# M220xc.net
KiCad netlist of a schematic drawn in EAGLE
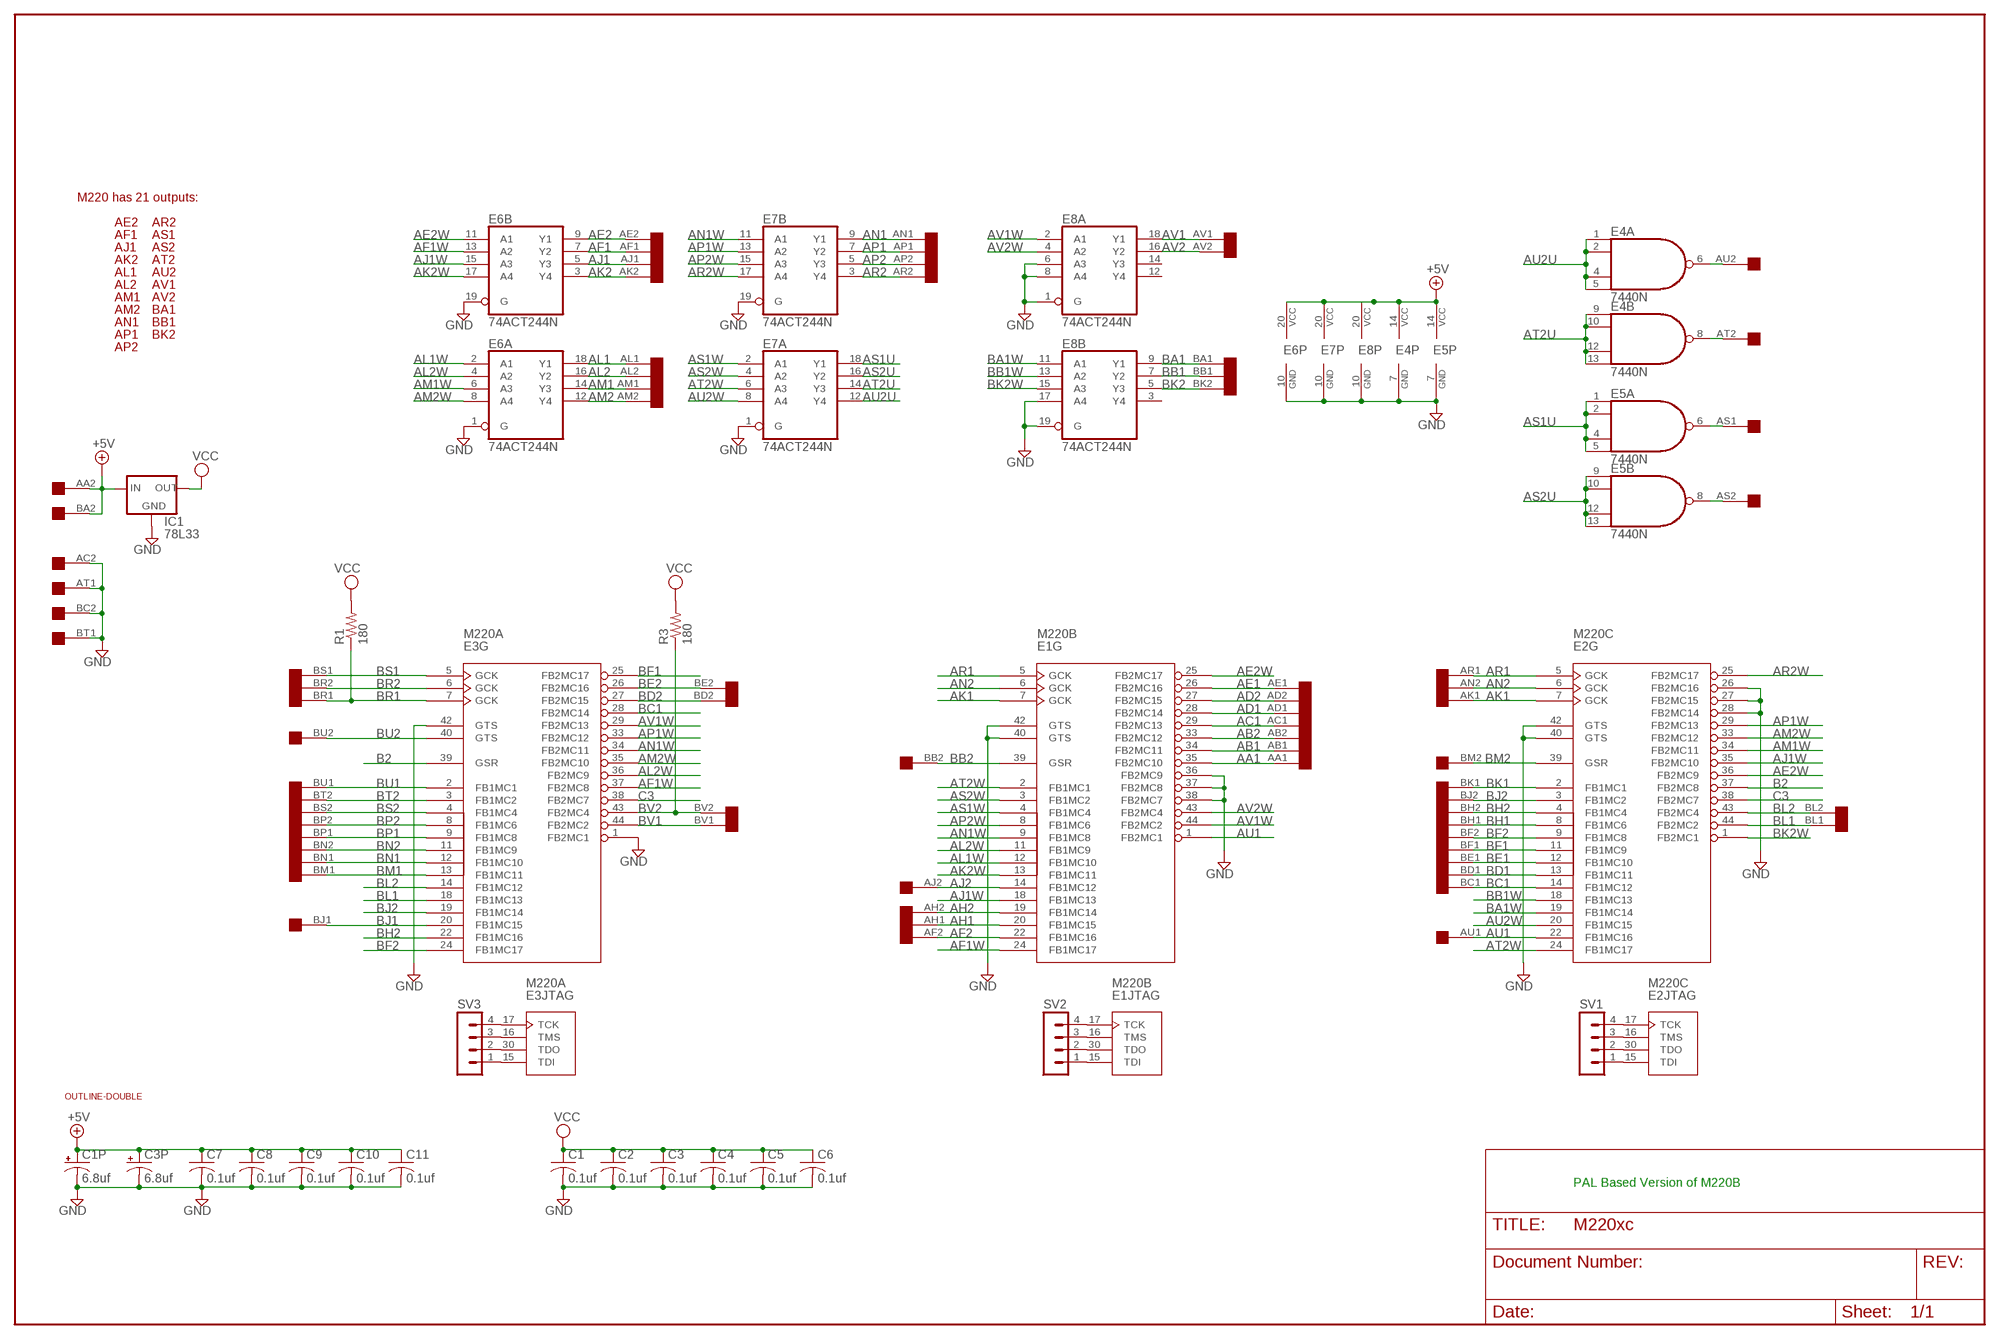
[diagram p0: schematic, sheet 1]

(export (version "E")
  (design (tool "Eeschema 10.0.6"))
  (components
    (comp (ref "C1")
      (value "0.1uf")
      (footprint "eagle-import:C050-025X075")
      (libsource (lib "eagle-import") (part "C-US050-025X075"))
    )
    (comp (ref "C1P")
      (value "6.8uf")
      (footprint "eagle-import:E15-5")
      (libsource (lib "eagle-import") (part "CPOL-USE15-5AXIAL"))
    )
    (comp (ref "C2")
      (value "0.1uf")
      (footprint "eagle-import:C050-025X075")
      (libsource (lib "eagle-import") (part "C-US050-025X075"))
    )
    (comp (ref "C3")
      (value "0.1uf")
      (footprint "eagle-import:C050-025X075")
      (libsource (lib "eagle-import") (part "C-US050-025X075"))
    )
    (comp (ref "C3P")
      (value "6.8uf")
      (footprint "eagle-import:E15-5")
      (libsource (lib "eagle-import") (part "CPOL-USE15-5AXIAL"))
    )
    (comp (ref "C4")
      (value "0.1uf")
      (footprint "eagle-import:C050-025X075")
      (libsource (lib "eagle-import") (part "C-US050-025X075"))
    )
    (comp (ref "C5")
      (value "0.1uf")
      (footprint "eagle-import:C050-025X075")
      (libsource (lib "eagle-import") (part "C-US050-025X075"))
    )
    (comp (ref "C6")
      (value "0.1uf")
      (footprint "eagle-import:C050-025X075")
      (libsource (lib "eagle-import") (part "C-US050-025X075"))
    )
    (comp (ref "C7")
      (value "0.1uf")
      (footprint "eagle-import:C050-025X075")
      (libsource (lib "eagle-import") (part "C-US050-025X075"))
    )
    (comp (ref "C8")
      (value "0.1uf")
      (footprint "eagle-import:C050-025X075")
      (libsource (lib "eagle-import") (part "C-US050-025X075"))
    )
    (comp (ref "C9")
      (value "0.1uf")
      (footprint "eagle-import:C050-025X075")
      (libsource (lib "eagle-import") (part "C-US050-025X075"))
    )
    (comp (ref "C10")
      (value "0.1uf")
      (footprint "eagle-import:C050-025X075")
      (libsource (lib "eagle-import") (part "C-US050-025X075"))
    )
    (comp (ref "C11")
      (value "0.1uf")
      (footprint "eagle-import:C050-025X075")
      (libsource (lib "eagle-import") (part "C-US050-025X075"))
    )
    (comp (ref "E1")
      (value "M220B")
      (footprint "eagle-import:PLCC-S44")
      (libsource (lib "eagle-import") (part "XC9536-44"))
    )
    (comp (ref "E2")
      (value "M220C")
      (footprint "eagle-import:PLCC-S44")
      (libsource (lib "eagle-import") (part "XC9536-44"))
    )
    (comp (ref "E3")
      (value "M220A")
      (footprint "eagle-import:PLCC-S44")
      (libsource (lib "eagle-import") (part "XC9536-44"))
    )
    (comp (ref "E4")
      (value "7440N")
      (footprint "eagle-import:DIL14")
      (libsource (lib "eagle-import") (part "7420NS"))
    )
    (comp (ref "E5")
      (value "7440N")
      (footprint "eagle-import:DIL14")
      (libsource (lib "eagle-import") (part "7420NS"))
    )
    (comp (ref "E6")
      (value "74ACT244N")
      (footprint "eagle-import:DIL20")
      (libsource (lib "eagle-import") (part "74244NS"))
    )
    (comp (ref "E7")
      (value "74ACT244N")
      (footprint "eagle-import:DIL20")
      (libsource (lib "eagle-import") (part "74244NS"))
    )
    (comp (ref "E8")
      (value "74ACT244N")
      (footprint "eagle-import:DIL20")
      (libsource (lib "eagle-import") (part "74244NS"))
    )
    (comp (ref "IC1")
      (value "78L33")
      (footprint "eagle-import:78LXX")
      (libsource (lib "eagle-import") (part "78LXX"))
    )
    (comp (ref "R1")
      (value "180")
      (footprint "eagle-import:0207_10")
      (libsource (lib "eagle-import") (part "R-US_0207/10"))
    )
    (comp (ref "R3")
      (value "180")
      (footprint "eagle-import:0207_10")
      (libsource (lib "eagle-import") (part "R-US_0207/10"))
    )
    (comp (ref "SV1")
      (value "MA04-1")
      (footprint "eagle-import:MA04-1")
      (libsource (lib "eagle-import") (part "MA04-1"))
    )
    (comp (ref "SV2")
      (value "MA04-1")
      (footprint "eagle-import:MA04-1")
      (libsource (lib "eagle-import") (part "MA04-1"))
    )
    (comp (ref "SV3")
      (value "MA04-1")
      (footprint "eagle-import:MA04-1")
      (libsource (lib "eagle-import") (part "MA04-1"))
    )
    (comp (ref "U$1")
      (value "DOUBLE")
      (footprint "eagle-import:EDGE-CON4")
      (libsource (lib "eagle-import") (part "DOUBLE"))
    )
    (comp (ref "U$2")
      (value "OUTLINE-DOUBLE")
      (footprint "eagle-import:DOUBLE")
      (libsource (lib "eagle-import") (part "OUTLINE-DOUBLE"))
    )
  )
  (nets
    (net (code "1") (name "+5V") (class "Default")
      (node (ref "C10") (pin "1") (pinfunction "1_1") (pintype "passive"))
      (node (ref "C11") (pin "1") (pinfunction "1_1") (pintype "passive"))
      (node (ref "C1P") (pin "+") (pinfunction "+_+") (pintype "passive"))
      (node (ref "C3P") (pin "+") (pinfunction "+_+") (pintype "passive"))
      (node (ref "C7") (pin "1") (pinfunction "1_1") (pintype "passive"))
      (node (ref "C8") (pin "1") (pinfunction "1_1") (pintype "passive"))
      (node (ref "C9") (pin "1") (pinfunction "1_1") (pintype "passive"))
      (node (ref "E4") (pin "14") (pinfunction "VCC_14") (pintype "power_in"))
      (node (ref "E5") (pin "14") (pinfunction "VCC_14") (pintype "power_in"))
      (node (ref "E6") (pin "20") (pinfunction "VCC_20") (pintype "power_in"))
      (node (ref "E7") (pin "20") (pinfunction "VCC_20") (pintype "power_in"))
      (node (ref "E8") (pin "20") (pinfunction "VCC_20") (pintype "power_in"))
      (node (ref "IC1") (pin "IN") (pinfunction "IN_IN") (pintype "input"))
      (node (ref "U$1") (pin "AA2") (pinfunction "1_AA2") (pintype "bidirectional"))
      (node (ref "U$1") (pin "BA2") (pinfunction "1_BA2") (pintype "bidirectional"))
    )
    (net (code "2") (name "/AA1") (class "Default")
      (node (ref "E1") (pin "35") (pinfunction "FB2MC10_35") (pintype "bidirectional"))
      (node (ref "U$1") (pin "AA1") (pinfunction "1_AA1") (pintype "bidirectional"))
    )
    (net (code "3") (name "/AB1") (class "Default")
      (node (ref "E1") (pin "34") (pinfunction "FB2MC11_34") (pintype "bidirectional"))
      (node (ref "U$1") (pin "AB1") (pinfunction "1_AB1") (pintype "bidirectional"))
    )
    (net (code "4") (name "/AB2") (class "Default")
      (node (ref "E1") (pin "33") (pinfunction "FB2MC12_33") (pintype "bidirectional"))
      (node (ref "U$1") (pin "AB2") (pinfunction "1_AB2") (pintype "bidirectional"))
    )
    (net (code "5") (name "/AC1") (class "Default")
      (node (ref "E1") (pin "29") (pinfunction "FB2MC13_29") (pintype "bidirectional"))
      (node (ref "U$1") (pin "AC1") (pinfunction "1_AC1") (pintype "bidirectional"))
    )
    (net (code "6") (name "/AD1") (class "Default")
      (node (ref "E1") (pin "28") (pinfunction "FB2MC14_28") (pintype "bidirectional"))
      (node (ref "U$1") (pin "AD1") (pinfunction "1_AD1") (pintype "bidirectional"))
    )
    (net (code "7") (name "/AD2") (class "Default")
      (node (ref "E1") (pin "27") (pinfunction "FB2MC15_27") (pintype "bidirectional"))
      (node (ref "U$1") (pin "AD2") (pinfunction "1_AD2") (pintype "bidirectional"))
    )
    (net (code "8") (name "/AE1") (class "Default")
      (node (ref "E1") (pin "26") (pinfunction "FB2MC16_26") (pintype "bidirectional"))
      (node (ref "U$1") (pin "AE1") (pinfunction "1_AE1") (pintype "bidirectional"))
    )
    (net (code "9") (name "/AE2") (class "Default")
      (node (ref "E6") (pin "9") (pinfunction "Y1_9") (pintype "tri_state"))
      (node (ref "U$1") (pin "AE2") (pinfunction "1_AE2") (pintype "bidirectional"))
    )
    (net (code "10") (name "/AE2W") (class "Default")
      (node (ref "E1") (pin "25") (pinfunction "FB2MC17_25") (pintype "bidirectional"))
      (node (ref "E2") (pin "36") (pinfunction "FB2MC9_36") (pintype "bidirectional"))
      (node (ref "E6") (pin "11") (pinfunction "A1_11") (pintype "input"))
    )
    (net (code "11") (name "/AF1") (class "Default")
      (node (ref "E6") (pin "7") (pinfunction "Y2_7") (pintype "tri_state"))
      (node (ref "U$1") (pin "AF1") (pinfunction "1_AF1") (pintype "bidirectional"))
    )
    (net (code "12") (name "/AF1W") (class "Default")
      (node (ref "E1") (pin "24") (pinfunction "FB1MC17_24") (pintype "bidirectional"))
      (node (ref "E3") (pin "37") (pinfunction "FB2MC8_37") (pintype "bidirectional"))
      (node (ref "E6") (pin "13") (pinfunction "A2_13") (pintype "input"))
    )
    (net (code "13") (name "/AF2") (class "Default")
      (node (ref "E1") (pin "22") (pinfunction "FB1MC16_22") (pintype "bidirectional"))
      (node (ref "U$1") (pin "AF2") (pinfunction "1_AF2") (pintype "bidirectional"))
    )
    (net (code "14") (name "/AH1") (class "Default")
      (node (ref "E1") (pin "20") (pinfunction "FB1MC15_20") (pintype "bidirectional"))
      (node (ref "U$1") (pin "AH1") (pinfunction "1_AH1") (pintype "bidirectional"))
    )
    (net (code "15") (name "/AH2") (class "Default")
      (node (ref "E1") (pin "19") (pinfunction "FB1MC14_19") (pintype "bidirectional"))
      (node (ref "U$1") (pin "AH2") (pinfunction "1_AH2") (pintype "bidirectional"))
    )
    (net (code "16") (name "/AJ1") (class "Default")
      (node (ref "E6") (pin "5") (pinfunction "Y3_5") (pintype "tri_state"))
      (node (ref "U$1") (pin "AJ1") (pinfunction "1_AJ1") (pintype "bidirectional"))
    )
    (net (code "17") (name "/AJ1W") (class "Default")
      (node (ref "E1") (pin "18") (pinfunction "FB1MC13_18") (pintype "bidirectional"))
      (node (ref "E2") (pin "35") (pinfunction "FB2MC10_35") (pintype "bidirectional"))
      (node (ref "E6") (pin "15") (pinfunction "A3_15") (pintype "input"))
    )
    (net (code "18") (name "/AJ2") (class "Default")
      (node (ref "E1") (pin "14") (pinfunction "FB1MC12_14") (pintype "bidirectional"))
      (node (ref "U$1") (pin "AJ2") (pinfunction "1_AJ2") (pintype "bidirectional"))
    )
    (net (code "19") (name "/AK1") (class "Default")
      (node (ref "E1") (pin "7") (pinfunction "GCK_7") (pintype "input"))
      (node (ref "E2") (pin "7") (pinfunction "GCK_7") (pintype "input"))
      (node (ref "U$1") (pin "AK1") (pinfunction "1_AK1") (pintype "bidirectional"))
    )
    (net (code "20") (name "/AK2") (class "Default")
      (node (ref "E6") (pin "3") (pinfunction "Y4_3") (pintype "tri_state"))
      (node (ref "U$1") (pin "AK2") (pinfunction "1_AK2") (pintype "bidirectional"))
    )
    (net (code "21") (name "/AK2W") (class "Default")
      (node (ref "E1") (pin "13") (pinfunction "FB1MC11_13") (pintype "bidirectional"))
      (node (ref "E6") (pin "17") (pinfunction "A4_17") (pintype "input"))
    )
    (net (code "22") (name "/AL1") (class "Default")
      (node (ref "E6") (pin "18") (pinfunction "Y1_18") (pintype "tri_state"))
      (node (ref "U$1") (pin "AL1") (pinfunction "1_AL1") (pintype "bidirectional"))
    )
    (net (code "23") (name "/AL1W") (class "Default")
      (node (ref "E1") (pin "12") (pinfunction "FB1MC10_12") (pintype "bidirectional"))
      (node (ref "E6") (pin "2") (pinfunction "A1_2") (pintype "input"))
    )
    (net (code "24") (name "/AL2") (class "Default")
      (node (ref "E6") (pin "16") (pinfunction "Y2_16") (pintype "tri_state"))
      (node (ref "U$1") (pin "AL2") (pinfunction "1_AL2") (pintype "bidirectional"))
    )
    (net (code "25") (name "/AL2W") (class "Default")
      (node (ref "E1") (pin "11") (pinfunction "FB1MC9_11") (pintype "bidirectional"))
      (node (ref "E3") (pin "36") (pinfunction "FB2MC9_36") (pintype "bidirectional"))
      (node (ref "E6") (pin "4") (pinfunction "A2_4") (pintype "input"))
    )
    (net (code "26") (name "/AM1") (class "Default")
      (node (ref "E6") (pin "14") (pinfunction "Y3_14") (pintype "tri_state"))
      (node (ref "U$1") (pin "AM1") (pinfunction "1_AM1") (pintype "bidirectional"))
    )
    (net (code "27") (name "/AM1W") (class "Default")
      (node (ref "E2") (pin "34") (pinfunction "FB2MC11_34") (pintype "bidirectional"))
      (node (ref "E6") (pin "6") (pinfunction "A3_6") (pintype "input"))
    )
    (net (code "28") (name "/AM2") (class "Default")
      (node (ref "E6") (pin "12") (pinfunction "Y4_12") (pintype "tri_state"))
      (node (ref "U$1") (pin "AM2") (pinfunction "1_AM2") (pintype "bidirectional"))
    )
    (net (code "29") (name "/AM2W") (class "Default")
      (node (ref "E2") (pin "33") (pinfunction "FB2MC12_33") (pintype "bidirectional"))
      (node (ref "E3") (pin "35") (pinfunction "FB2MC10_35") (pintype "bidirectional"))
      (node (ref "E6") (pin "8") (pinfunction "A4_8") (pintype "input"))
    )
    (net (code "30") (name "/AN1") (class "Default")
      (node (ref "E7") (pin "9") (pinfunction "Y1_9") (pintype "tri_state"))
      (node (ref "U$1") (pin "AN1") (pinfunction "1_AN1") (pintype "bidirectional"))
    )
    (net (code "31") (name "/AN1W") (class "Default")
      (node (ref "E1") (pin "9") (pinfunction "FB1MC8_9") (pintype "bidirectional"))
      (node (ref "E3") (pin "34") (pinfunction "FB2MC11_34") (pintype "bidirectional"))
      (node (ref "E7") (pin "11") (pinfunction "A1_11") (pintype "input"))
    )
    (net (code "32") (name "/AN2") (class "Default")
      (node (ref "E1") (pin "6") (pinfunction "GCK_6") (pintype "input"))
      (node (ref "E2") (pin "6") (pinfunction "GCK_6") (pintype "input"))
      (node (ref "U$1") (pin "AN2") (pinfunction "1_AN2") (pintype "bidirectional"))
    )
    (net (code "33") (name "/AP1") (class "Default")
      (node (ref "E7") (pin "7") (pinfunction "Y2_7") (pintype "tri_state"))
      (node (ref "U$1") (pin "AP1") (pinfunction "1_AP1") (pintype "bidirectional"))
    )
    (net (code "34") (name "/AP1W") (class "Default")
      (node (ref "E2") (pin "29") (pinfunction "FB2MC13_29") (pintype "bidirectional"))
      (node (ref "E3") (pin "33") (pinfunction "FB2MC12_33") (pintype "bidirectional"))
      (node (ref "E7") (pin "13") (pinfunction "A2_13") (pintype "input"))
    )
    (net (code "35") (name "/AP2") (class "Default")
      (node (ref "E7") (pin "5") (pinfunction "Y3_5") (pintype "tri_state"))
      (node (ref "U$1") (pin "AP2") (pinfunction "1_AP2") (pintype "bidirectional"))
    )
    (net (code "36") (name "/AP2W") (class "Default")
      (node (ref "E1") (pin "8") (pinfunction "FB1MC6_8") (pintype "bidirectional"))
      (node (ref "E7") (pin "15") (pinfunction "A3_15") (pintype "input"))
    )
    (net (code "37") (name "/AR1") (class "Default")
      (node (ref "E1") (pin "5") (pinfunction "GCK_5") (pintype "input"))
      (node (ref "E2") (pin "5") (pinfunction "GCK_5") (pintype "input"))
      (node (ref "U$1") (pin "AR1") (pinfunction "1_AR1") (pintype "bidirectional"))
    )
    (net (code "38") (name "/AR2") (class "Default")
      (node (ref "E7") (pin "3") (pinfunction "Y4_3") (pintype "tri_state"))
      (node (ref "U$1") (pin "AR2") (pinfunction "1_AR2") (pintype "bidirectional"))
    )
    (net (code "39") (name "/AR2W") (class "Default")
      (node (ref "E2") (pin "25") (pinfunction "FB2MC17_25") (pintype "bidirectional"))
      (node (ref "E7") (pin "17") (pinfunction "A4_17") (pintype "input"))
    )
    (net (code "40") (name "/AS1U") (class "Default")
      (node (ref "E5") (pin "1") (pinfunction "I0_1") (pintype "input"))
      (node (ref "E5") (pin "2") (pinfunction "I1_2") (pintype "input"))
      (node (ref "E5") (pin "4") (pinfunction "I2_4") (pintype "input"))
      (node (ref "E5") (pin "5") (pinfunction "I3_5") (pintype "input"))
      (node (ref "E7") (pin "18") (pinfunction "Y1_18") (pintype "tri_state"))
    )
    (net (code "41") (name "/AS1W") (class "Default")
      (node (ref "E1") (pin "4") (pinfunction "FB1MC4_4") (pintype "bidirectional"))
      (node (ref "E7") (pin "2") (pinfunction "A1_2") (pintype "input"))
    )
    (net (code "42") (name "/AS2U") (class "Default")
      (node (ref "E5") (pin "10") (pinfunction "I1_10") (pintype "input"))
      (node (ref "E5") (pin "12") (pinfunction "I2_12") (pintype "input"))
      (node (ref "E5") (pin "13") (pinfunction "I3_13") (pintype "input"))
      (node (ref "E5") (pin "9") (pinfunction "I0_9") (pintype "input"))
      (node (ref "E7") (pin "16") (pinfunction "Y2_16") (pintype "tri_state"))
    )
    (net (code "43") (name "/AS2W") (class "Default")
      (node (ref "E1") (pin "3") (pinfunction "FB1MC2_3") (pintype "bidirectional"))
      (node (ref "E7") (pin "4") (pinfunction "A2_4") (pintype "input"))
    )
    (net (code "44") (name "/AT2U") (class "Default")
      (node (ref "E4") (pin "10") (pinfunction "I1_10") (pintype "input"))
      (node (ref "E4") (pin "12") (pinfunction "I2_12") (pintype "input"))
      (node (ref "E4") (pin "13") (pinfunction "I3_13") (pintype "input"))
      (node (ref "E4") (pin "9") (pinfunction "I0_9") (pintype "input"))
      (node (ref "E7") (pin "14") (pinfunction "Y3_14") (pintype "tri_state"))
    )
    (net (code "45") (name "/AT2W") (class "Default")
      (node (ref "E1") (pin "2") (pinfunction "FB1MC1_2") (pintype "bidirectional"))
      (node (ref "E2") (pin "24") (pinfunction "FB1MC17_24") (pintype "bidirectional"))
      (node (ref "E7") (pin "6") (pinfunction "A3_6") (pintype "input"))
    )
    (net (code "46") (name "/AU1") (class "Default")
      (node (ref "E1") (pin "1") (pinfunction "FB2MC1_1") (pintype "bidirectional"))
      (node (ref "E2") (pin "22") (pinfunction "FB1MC16_22") (pintype "bidirectional"))
      (node (ref "U$1") (pin "AU1") (pinfunction "1_AU1") (pintype "bidirectional"))
    )
    (net (code "47") (name "/AU2U") (class "Default")
      (node (ref "E4") (pin "1") (pinfunction "I0_1") (pintype "input"))
      (node (ref "E4") (pin "2") (pinfunction "I1_2") (pintype "input"))
      (node (ref "E4") (pin "4") (pinfunction "I2_4") (pintype "input"))
      (node (ref "E4") (pin "5") (pinfunction "I3_5") (pintype "input"))
      (node (ref "E7") (pin "12") (pinfunction "Y4_12") (pintype "tri_state"))
    )
    (net (code "48") (name "/AU2W") (class "Default")
      (node (ref "E2") (pin "20") (pinfunction "FB1MC15_20") (pintype "bidirectional"))
      (node (ref "E7") (pin "8") (pinfunction "A4_8") (pintype "input"))
    )
    (net (code "49") (name "/AV1") (class "Default")
      (node (ref "E8") (pin "18") (pinfunction "Y1_18") (pintype "tri_state"))
      (node (ref "U$1") (pin "AV1") (pinfunction "1_AV1") (pintype "bidirectional"))
    )
    (net (code "50") (name "/AV1W") (class "Default")
      (node (ref "E1") (pin "44") (pinfunction "FB2MC2_44") (pintype "bidirectional"))
      (node (ref "E3") (pin "29") (pinfunction "FB2MC13_29") (pintype "bidirectional"))
      (node (ref "E8") (pin "2") (pinfunction "A1_2") (pintype "input"))
    )
    (net (code "51") (name "/AV2") (class "Default")
      (node (ref "E8") (pin "16") (pinfunction "Y2_16") (pintype "tri_state"))
      (node (ref "U$1") (pin "AV2") (pinfunction "1_AV2") (pintype "bidirectional"))
    )
    (net (code "52") (name "/AV2W") (class "Default")
      (node (ref "E1") (pin "43") (pinfunction "FB2MC4_43") (pintype "bidirectional"))
      (node (ref "E8") (pin "4") (pinfunction "A2_4") (pintype "input"))
    )
    (net (code "53") (name "/B2") (class "Default")
      (node (ref "E2") (pin "37") (pinfunction "FB2MC8_37") (pintype "bidirectional"))
      (node (ref "E3") (pin "39") (pinfunction "GSR_39") (pintype "input"))
    )
    (net (code "54") (name "/BA1") (class "Default")
      (node (ref "E8") (pin "9") (pinfunction "Y1_9") (pintype "tri_state"))
      (node (ref "U$1") (pin "BA1") (pinfunction "1_BA1") (pintype "bidirectional"))
    )
    (net (code "55") (name "/BA1W") (class "Default")
      (node (ref "E2") (pin "19") (pinfunction "FB1MC14_19") (pintype "bidirectional"))
      (node (ref "E8") (pin "11") (pinfunction "A1_11") (pintype "input"))
    )
    (net (code "56") (name "/BB1") (class "Default")
      (node (ref "E8") (pin "7") (pinfunction "Y2_7") (pintype "tri_state"))
      (node (ref "U$1") (pin "BB1") (pinfunction "1_BB1") (pintype "bidirectional"))
    )
    (net (code "57") (name "/BB1W") (class "Default")
      (node (ref "E2") (pin "18") (pinfunction "FB1MC13_18") (pintype "bidirectional"))
      (node (ref "E8") (pin "13") (pinfunction "A2_13") (pintype "input"))
    )
    (net (code "58") (name "/BB2") (class "Default")
      (node (ref "E1") (pin "39") (pinfunction "GSR_39") (pintype "input"))
      (node (ref "U$1") (pin "BB2") (pinfunction "1_BB2") (pintype "bidirectional"))
    )
    (net (code "59") (name "/BC1") (class "Default")
      (node (ref "E2") (pin "14") (pinfunction "FB1MC12_14") (pintype "bidirectional"))
      (node (ref "E3") (pin "28") (pinfunction "FB2MC14_28") (pintype "bidirectional"))
      (node (ref "U$1") (pin "BC1") (pinfunction "1_BC1") (pintype "bidirectional"))
    )
    (net (code "60") (name "/BD1") (class "Default")
      (node (ref "E2") (pin "13") (pinfunction "FB1MC11_13") (pintype "bidirectional"))
      (node (ref "U$1") (pin "BD1") (pinfunction "1_BD1") (pintype "bidirectional"))
    )
    (net (code "61") (name "/BD2") (class "Default")
      (node (ref "E3") (pin "27") (pinfunction "FB2MC15_27") (pintype "bidirectional"))
      (node (ref "U$1") (pin "BD2") (pinfunction "1_BD2") (pintype "bidirectional"))
    )
    (net (code "62") (name "/BE1") (class "Default")
      (node (ref "E2") (pin "12") (pinfunction "FB1MC10_12") (pintype "bidirectional"))
      (node (ref "U$1") (pin "BE1") (pinfunction "1_BE1") (pintype "bidirectional"))
    )
    (net (code "63") (name "/BE2") (class "Default")
      (node (ref "E3") (pin "26") (pinfunction "FB2MC16_26") (pintype "bidirectional"))
      (node (ref "U$1") (pin "BE2") (pinfunction "1_BE2") (pintype "bidirectional"))
    )
    (net (code "64") (name "/BF1") (class "Default")
      (node (ref "E2") (pin "11") (pinfunction "FB1MC9_11") (pintype "bidirectional"))
      (node (ref "E3") (pin "25") (pinfunction "FB2MC17_25") (pintype "bidirectional"))
      (node (ref "U$1") (pin "BF1") (pinfunction "1_BF1") (pintype "bidirectional"))
    )
    (net (code "65") (name "/BF2") (class "Default")
      (node (ref "E2") (pin "9") (pinfunction "FB1MC8_9") (pintype "bidirectional"))
      (node (ref "E3") (pin "24") (pinfunction "FB1MC17_24") (pintype "bidirectional"))
      (node (ref "U$1") (pin "BF2") (pinfunction "1_BF2") (pintype "bidirectional"))
    )
    (net (code "66") (name "/BH1") (class "Default")
      (node (ref "E2") (pin "8") (pinfunction "FB1MC6_8") (pintype "bidirectional"))
      (node (ref "U$1") (pin "BH1") (pinfunction "1_BH1") (pintype "bidirectional"))
    )
    (net (code "67") (name "/BH2") (class "Default")
      (node (ref "E2") (pin "4") (pinfunction "FB1MC4_4") (pintype "bidirectional"))
      (node (ref "E3") (pin "22") (pinfunction "FB1MC16_22") (pintype "bidirectional"))
      (node (ref "U$1") (pin "BH2") (pinfunction "1_BH2") (pintype "bidirectional"))
    )
    (net (code "68") (name "/BJ1") (class "Default")
      (node (ref "E3") (pin "20") (pinfunction "FB1MC15_20") (pintype "bidirectional"))
      (node (ref "U$1") (pin "BJ1") (pinfunction "1_BJ1") (pintype "bidirectional"))
    )
    (net (code "69") (name "/BJ2") (class "Default")
      (node (ref "E2") (pin "3") (pinfunction "FB1MC2_3") (pintype "bidirectional"))
      (node (ref "E3") (pin "19") (pinfunction "FB1MC14_19") (pintype "bidirectional"))
      (node (ref "U$1") (pin "BJ2") (pinfunction "1_BJ2") (pintype "bidirectional"))
    )
    (net (code "70") (name "/BK1") (class "Default")
      (node (ref "E2") (pin "2") (pinfunction "FB1MC1_2") (pintype "bidirectional"))
      (node (ref "U$1") (pin "BK1") (pinfunction "1_BK1") (pintype "bidirectional"))
    )
    (net (code "71") (name "/BK2") (class "Default")
      (node (ref "E8") (pin "5") (pinfunction "Y3_5") (pintype "tri_state"))
      (node (ref "U$1") (pin "BK2") (pinfunction "1_BK2") (pintype "bidirectional"))
    )
    (net (code "72") (name "/BK2W") (class "Default")
      (node (ref "E2") (pin "1") (pinfunction "FB2MC1_1") (pintype "bidirectional"))
      (node (ref "E8") (pin "15") (pinfunction "A3_15") (pintype "input"))
    )
    (net (code "73") (name "/BL1") (class "Default")
      (node (ref "E2") (pin "44") (pinfunction "FB2MC2_44") (pintype "bidirectional"))
      (node (ref "E3") (pin "18") (pinfunction "FB1MC13_18") (pintype "bidirectional"))
      (node (ref "U$1") (pin "BL1") (pinfunction "1_BL1") (pintype "bidirectional"))
    )
    (net (code "74") (name "/BL2") (class "Default")
      (node (ref "E2") (pin "43") (pinfunction "FB2MC4_43") (pintype "bidirectional"))
      (node (ref "E3") (pin "14") (pinfunction "FB1MC12_14") (pintype "bidirectional"))
      (node (ref "U$1") (pin "BL2") (pinfunction "1_BL2") (pintype "bidirectional"))
    )
    (net (code "75") (name "/BM1") (class "Default")
      (node (ref "E3") (pin "13") (pinfunction "FB1MC11_13") (pintype "bidirectional"))
      (node (ref "U$1") (pin "BM1") (pinfunction "1_BM1") (pintype "bidirectional"))
    )
    (net (code "76") (name "/BM2") (class "Default")
      (node (ref "E2") (pin "39") (pinfunction "GSR_39") (pintype "input"))
      (node (ref "U$1") (pin "BM2") (pinfunction "1_BM2") (pintype "bidirectional"))
    )
    (net (code "77") (name "/BN1") (class "Default")
      (node (ref "E3") (pin "12") (pinfunction "FB1MC10_12") (pintype "bidirectional"))
      (node (ref "U$1") (pin "BN1") (pinfunction "1_BN1") (pintype "bidirectional"))
    )
    (net (code "78") (name "/BN2") (class "Default")
      (node (ref "E3") (pin "11") (pinfunction "FB1MC9_11") (pintype "bidirectional"))
      (node (ref "U$1") (pin "BN2") (pinfunction "1_BN2") (pintype "bidirectional"))
    )
    (net (code "79") (name "/BP1") (class "Default")
      (node (ref "E3") (pin "9") (pinfunction "FB1MC8_9") (pintype "bidirectional"))
      (node (ref "U$1") (pin "BP1") (pinfunction "1_BP1") (pintype "bidirectional"))
    )
    (net (code "80") (name "/BP2") (class "Default")
      (node (ref "E3") (pin "8") (pinfunction "FB1MC6_8") (pintype "bidirectional"))
      (node (ref "U$1") (pin "BP2") (pinfunction "1_BP2") (pintype "bidirectional"))
    )
    (net (code "81") (name "/BR1") (class "Default")
      (node (ref "E3") (pin "7") (pinfunction "GCK_7") (pintype "input"))
      (node (ref "R1") (pin "1") (pinfunction "1_1") (pintype "passive"))
      (node (ref "U$1") (pin "BR1") (pinfunction "1_BR1") (pintype "bidirectional"))
    )
    (net (code "82") (name "/BR2") (class "Default")
      (node (ref "E3") (pin "6") (pinfunction "GCK_6") (pintype "input"))
      (node (ref "U$1") (pin "BR2") (pinfunction "1_BR2") (pintype "bidirectional"))
    )
    (net (code "83") (name "/BS1") (class "Default")
      (node (ref "E3") (pin "5") (pinfunction "GCK_5") (pintype "input"))
      (node (ref "U$1") (pin "BS1") (pinfunction "1_BS1") (pintype "bidirectional"))
    )
    (net (code "84") (name "/BS2") (class "Default")
      (node (ref "E3") (pin "4") (pinfunction "FB1MC4_4") (pintype "bidirectional"))
      (node (ref "U$1") (pin "BS2") (pinfunction "1_BS2") (pintype "bidirectional"))
    )
    (net (code "85") (name "/BT2") (class "Default")
      (node (ref "E3") (pin "3") (pinfunction "FB1MC2_3") (pintype "bidirectional"))
      (node (ref "U$1") (pin "BT2") (pinfunction "1_BT2") (pintype "bidirectional"))
    )
    (net (code "86") (name "/BU1") (class "Default")
      (node (ref "E3") (pin "2") (pinfunction "FB1MC1_2") (pintype "bidirectional"))
      (node (ref "U$1") (pin "BU1") (pinfunction "1_BU1") (pintype "bidirectional"))
    )
    (net (code "87") (name "/BU2") (class "Default")
      (node (ref "E3") (pin "40") (pinfunction "GTS_40") (pintype "input"))
      (node (ref "U$1") (pin "BU2") (pinfunction "1_BU2") (pintype "bidirectional"))
    )
    (net (code "88") (name "/BV1") (class "Default")
      (node (ref "E3") (pin "44") (pinfunction "FB2MC2_44") (pintype "bidirectional"))
      (node (ref "U$1") (pin "BV1") (pinfunction "1_BV1") (pintype "bidirectional"))
    )
    (net (code "89") (name "/BV2") (class "Default")
      (node (ref "E3") (pin "43") (pinfunction "FB2MC4_43") (pintype "bidirectional"))
      (node (ref "R3") (pin "1") (pinfunction "1_1") (pintype "passive"))
      (node (ref "U$1") (pin "BV2") (pinfunction "1_BV2") (pintype "bidirectional"))
    )
    (net (code "90") (name "/C3") (class "Default")
      (node (ref "E2") (pin "38") (pinfunction "FB2MC7_38") (pintype "bidirectional"))
      (node (ref "E3") (pin "38") (pinfunction "FB2MC7_38") (pintype "bidirectional"))
    )
    (net (code "91") (name "GND") (class "Default")
      (node (ref "C1") (pin "2") (pinfunction "2_2") (pintype "passive"))
      (node (ref "C10") (pin "2") (pinfunction "2_2") (pintype "passive"))
      (node (ref "C11") (pin "2") (pinfunction "2_2") (pintype "passive"))
      (node (ref "C1P") (pin "-") (pinfunction "-_-") (pintype "passive"))
      (node (ref "C2") (pin "2") (pinfunction "2_2") (pintype "passive"))
      (node (ref "C3") (pin "2") (pinfunction "2_2") (pintype "passive"))
      (node (ref "C3P") (pin "-") (pinfunction "-_-") (pintype "passive"))
      (node (ref "C4") (pin "2") (pinfunction "2_2") (pintype "passive"))
      (node (ref "C5") (pin "2") (pinfunction "2_2") (pintype "passive"))
      (node (ref "C6") (pin "2") (pinfunction "2_2") (pintype "passive"))
      (node (ref "C7") (pin "2") (pinfunction "2_2") (pintype "passive"))
      (node (ref "C8") (pin "2") (pinfunction "2_2") (pintype "passive"))
      (node (ref "C9") (pin "2") (pinfunction "2_2") (pintype "passive"))
      (node (ref "E1") (pin "36") (pinfunction "FB2MC9_36") (pintype "bidirectional"))
      (node (ref "E1") (pin "37") (pinfunction "FB2MC8_37") (pintype "bidirectional"))
      (node (ref "E1") (pin "38") (pinfunction "FB2MC7_38") (pintype "bidirectional"))
      (node (ref "E1") (pin "40") (pinfunction "GTS_40") (pintype "input"))
      (node (ref "E1") (pin "42") (pinfunction "GTS_42") (pintype "input"))
      (node (ref "E2") (pin "26") (pinfunction "FB2MC16_26") (pintype "bidirectional"))
      (node (ref "E2") (pin "27") (pinfunction "FB2MC15_27") (pintype "bidirectional"))
      (node (ref "E2") (pin "28") (pinfunction "FB2MC14_28") (pintype "bidirectional"))
      (node (ref "E2") (pin "40") (pinfunction "GTS_40") (pintype "input"))
      (node (ref "E2") (pin "42") (pinfunction "GTS_42") (pintype "input"))
      (node (ref "E3") (pin "1") (pinfunction "FB2MC1_1") (pintype "bidirectional"))
      (node (ref "E3") (pin "42") (pinfunction "GTS_42") (pintype "input"))
      (node (ref "E4") (pin "7") (pinfunction "GND_7") (pintype "power_in"))
      (node (ref "E5") (pin "7") (pinfunction "GND_7") (pintype "power_in"))
      (node (ref "E6") (pin "1") (pinfunction "G_1") (pintype "input"))
      (node (ref "E6") (pin "10") (pinfunction "GND_10") (pintype "power_in"))
      (node (ref "E6") (pin "19") (pinfunction "G_19") (pintype "input"))
      (node (ref "E7") (pin "1") (pinfunction "G_1") (pintype "input"))
      (node (ref "E7") (pin "10") (pinfunction "GND_10") (pintype "power_in"))
      (node (ref "E7") (pin "19") (pinfunction "G_19") (pintype "input"))
      (node (ref "E8") (pin "1") (pinfunction "G_1") (pintype "input"))
      (node (ref "E8") (pin "10") (pinfunction "GND_10") (pintype "power_in"))
      (node (ref "E8") (pin "17") (pinfunction "A4_17") (pintype "input"))
      (node (ref "E8") (pin "19") (pinfunction "G_19") (pintype "input"))
      (node (ref "E8") (pin "6") (pinfunction "A3_6") (pintype "input"))
      (node (ref "E8") (pin "8") (pinfunction "A4_8") (pintype "input"))
      (node (ref "IC1") (pin "GND") (pinfunction "GND_GND") (pintype "input"))
      (node (ref "U$1") (pin "AC2") (pinfunction "1_AC2") (pintype "bidirectional"))
      (node (ref "U$1") (pin "AT1") (pinfunction "1_AT1") (pintype "bidirectional"))
      (node (ref "U$1") (pin "BC2") (pinfunction "1_BC2") (pintype "bidirectional"))
      (node (ref "U$1") (pin "BT1") (pinfunction "1_BT1") (pintype "bidirectional"))
    )
    (net (code "92") (name "Net-(E1B-TCK)") (class "Default")
      (node (ref "E1") (pin "17") (pinfunction "TCK_17") (pintype "input"))
      (node (ref "SV2") (pin "4") (pinfunction "4_4") (pintype "passive"))
    )
    (net (code "93") (name "Net-(E1B-TDI)") (class "Default")
      (node (ref "E1") (pin "15") (pinfunction "TDI_15") (pintype "input"))
      (node (ref "SV2") (pin "1") (pinfunction "1_1") (pintype "passive"))
    )
    (net (code "94") (name "Net-(E1B-TDO)") (class "Default")
      (node (ref "E1") (pin "30") (pinfunction "TDO_30") (pintype "output"))
      (node (ref "SV2") (pin "2") (pinfunction "2_2") (pintype "passive"))
    )
    (net (code "95") (name "Net-(E1B-TMS)") (class "Default")
      (node (ref "E1") (pin "16") (pinfunction "TMS_16") (pintype "input"))
      (node (ref "SV2") (pin "3") (pinfunction "3_3") (pintype "passive"))
    )
    (net (code "96") (name "Net-(E2B-TCK)") (class "Default")
      (node (ref "E2") (pin "17") (pinfunction "TCK_17") (pintype "input"))
      (node (ref "SV1") (pin "4") (pinfunction "4_4") (pintype "passive"))
    )
    (net (code "97") (name "Net-(E2B-TDI)") (class "Default")
      (node (ref "E2") (pin "15") (pinfunction "TDI_15") (pintype "input"))
      (node (ref "SV1") (pin "1") (pinfunction "1_1") (pintype "passive"))
    )
    (net (code "98") (name "Net-(E2B-TDO)") (class "Default")
      (node (ref "E2") (pin "30") (pinfunction "TDO_30") (pintype "output"))
      (node (ref "SV1") (pin "2") (pinfunction "2_2") (pintype "passive"))
    )
    (net (code "99") (name "Net-(E2B-TMS)") (class "Default")
      (node (ref "E2") (pin "16") (pinfunction "TMS_16") (pintype "input"))
      (node (ref "SV1") (pin "3") (pinfunction "3_3") (pintype "passive"))
    )
    (net (code "100") (name "Net-(E3B-TCK)") (class "Default")
      (node (ref "E3") (pin "17") (pinfunction "TCK_17") (pintype "input"))
      (node (ref "SV3") (pin "4") (pinfunction "4_4") (pintype "passive"))
    )
    (net (code "101") (name "Net-(E3B-TDI)") (class "Default")
      (node (ref "E3") (pin "15") (pinfunction "TDI_15") (pintype "input"))
      (node (ref "SV3") (pin "1") (pinfunction "1_1") (pintype "passive"))
    )
    (net (code "102") (name "Net-(E3B-TDO)") (class "Default")
      (node (ref "E3") (pin "30") (pinfunction "TDO_30") (pintype "output"))
      (node (ref "SV3") (pin "2") (pinfunction "2_2") (pintype "passive"))
    )
    (net (code "103") (name "Net-(E3B-TMS)") (class "Default")
      (node (ref "E3") (pin "16") (pinfunction "TMS_16") (pintype "input"))
      (node (ref "SV3") (pin "3") (pinfunction "3_3") (pintype "passive"))
    )
    (net (code "104") (name "Net-(E4A-O)") (class "Default")
      (node (ref "E4") (pin "6") (pinfunction "O_6") (pintype "output"))
      (node (ref "U$1") (pin "AU2") (pinfunction "1_AU2") (pintype "bidirectional"))
    )
    (net (code "105") (name "Net-(E4B-O)") (class "Default")
      (node (ref "E4") (pin "8") (pinfunction "O_8") (pintype "output"))
      (node (ref "U$1") (pin "AT2") (pinfunction "1_AT2") (pintype "bidirectional"))
    )
    (net (code "106") (name "Net-(E5A-O)") (class "Default")
      (node (ref "E5") (pin "6") (pinfunction "O_6") (pintype "output"))
      (node (ref "U$1") (pin "AS1") (pinfunction "1_AS1") (pintype "bidirectional"))
    )
    (net (code "107") (name "Net-(E5B-O)") (class "Default")
      (node (ref "E5") (pin "8") (pinfunction "O_8") (pintype "output"))
      (node (ref "U$1") (pin "AS2") (pinfunction "1_AS2") (pintype "bidirectional"))
    )
    (net (code "108") (name "VCC") (class "Default")
      (node (ref "C1") (pin "1") (pinfunction "1_1") (pintype "passive"))
      (node (ref "C2") (pin "1") (pinfunction "1_1") (pintype "passive"))
      (node (ref "C3") (pin "1") (pinfunction "1_1") (pintype "passive"))
      (node (ref "C4") (pin "1") (pinfunction "1_1") (pintype "passive"))
      (node (ref "C5") (pin "1") (pinfunction "1_1") (pintype "passive"))
      (node (ref "C6") (pin "1") (pinfunction "1_1") (pintype "passive"))
      (node (ref "IC1") (pin "OUT") (pinfunction "OUT_OUT") (pintype "passive"))
      (node (ref "R1") (pin "2") (pinfunction "2_2") (pintype "passive"))
      (node (ref "R3") (pin "2") (pinfunction "2_2") (pintype "passive"))
    )
    (net (code "109") (name "unconnected-(E8A-Y3-Pad14)") (class "Default")
      (node (ref "E8") (pin "14") (pinfunction "Y3_14") (pintype "tri_state"))
    )
    (net (code "110") (name "unconnected-(E8A-Y4-Pad12)") (class "Default")
      (node (ref "E8") (pin "12") (pinfunction "Y4_12") (pintype "tri_state"))
    )
    (net (code "111") (name "unconnected-(E8B-Y4-Pad3)") (class "Default")
      (node (ref "E8") (pin "3") (pinfunction "Y4_3") (pintype "tri_state"))
    )
  )
)
